# Adafruit_SHT31_Breakout.net
KiCad netlist of a schematic drawn in EAGLE
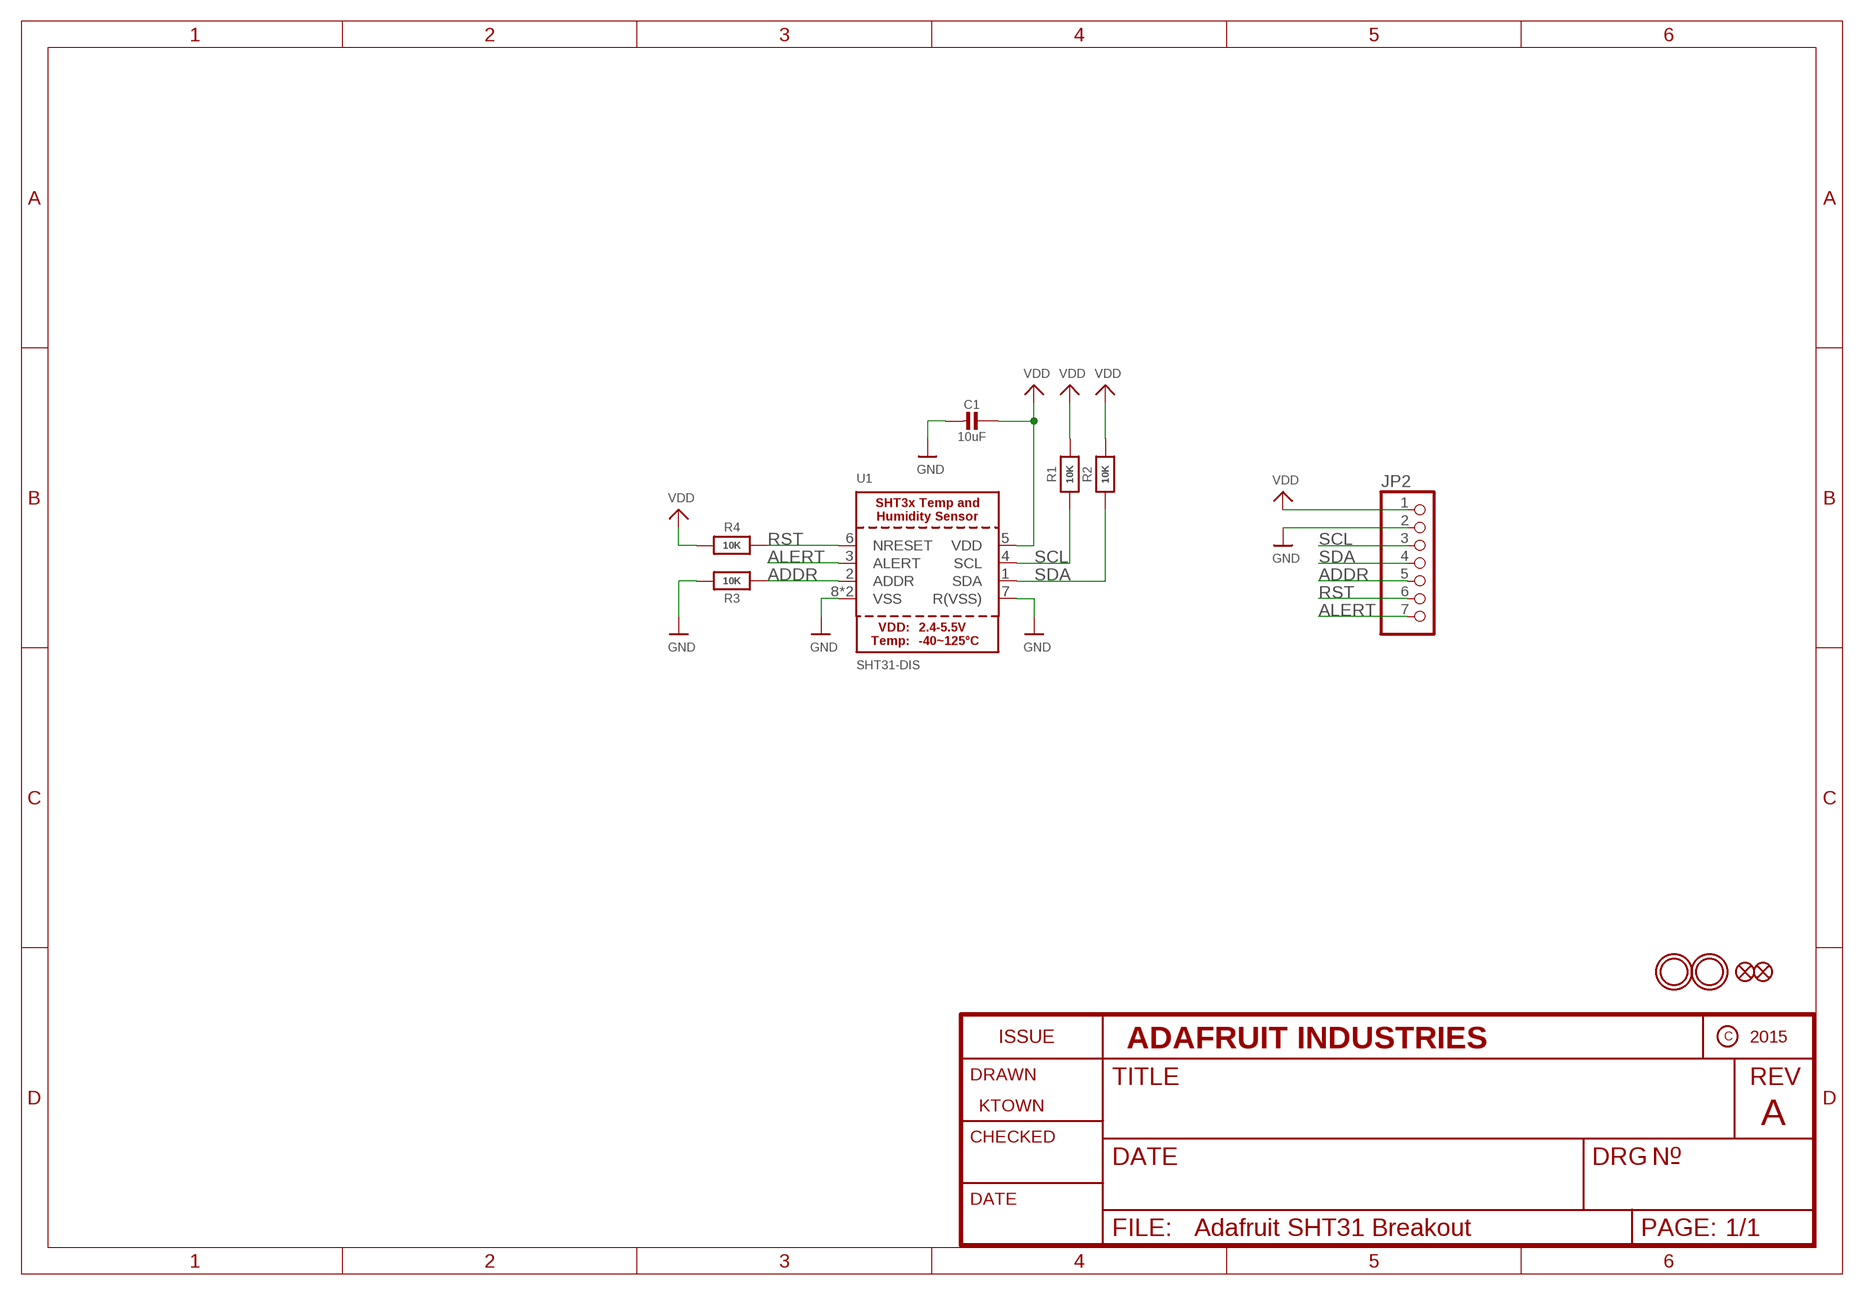
[diagram p0: schematic, sheet 1]

(export (version "E")
  (design (tool "Eeschema 10.0.6"))
  (components
    (comp (ref "C1")
      (value "10uF")
      (footprint "eagle-import:0805-NO")
      (libsource (lib "eagle-import") (part "CAP_CERAMIC0805-NOOUTLINE"))
    )
    (comp (ref "FID2")
      (value "FIDUCIAL\"\"")
      (footprint "eagle-import:FIDUCIAL_1MM")
      (libsource (lib "eagle-import") (part "FIDUCIAL{dblquote}{dblquote}"))
    )
    (comp (ref "FID3")
      (value "FIDUCIAL\"\"")
      (footprint "eagle-import:FIDUCIAL_1MM")
      (libsource (lib "eagle-import") (part "FIDUCIAL{dblquote}{dblquote}"))
    )
    (comp (ref "JP2")
      (value "HEADER-1X770MIL")
      (footprint "eagle-import:1X07_ROUND_70")
      (libsource (lib "eagle-import") (part "HEADER-1X770MIL"))
    )
    (comp (ref "R1")
      (value "10K")
      (footprint "eagle-import:0805-NO")
      (libsource (lib "eagle-import") (part "RESISTOR0805_NOOUTLINE"))
    )
    (comp (ref "R2")
      (value "10K")
      (footprint "eagle-import:0805-NO")
      (libsource (lib "eagle-import") (part "RESISTOR0805_NOOUTLINE"))
    )
    (comp (ref "R3")
      (value "10K")
      (footprint "eagle-import:_0805MP")
      (libsource (lib "eagle-import") (part "RESISTOR_0805MP"))
    )
    (comp (ref "R4")
      (value "10K")
      (footprint "eagle-import:0805-NO")
      (libsource (lib "eagle-import") (part "RESISTOR0805_NOOUTLINE"))
    )
    (comp (ref "U$1")
      (value "MOUNTINGHOLE2.5")
      (footprint "eagle-import:MOUNTINGHOLE_2.5_PLATED")
      (libsource (lib "eagle-import") (part "MOUNTINGHOLE2.5"))
    )
    (comp (ref "U$2")
      (value "MOUNTINGHOLE2.5")
      (footprint "eagle-import:MOUNTINGHOLE_2.5_PLATED")
      (libsource (lib "eagle-import") (part "MOUNTINGHOLE2.5"))
    )
    (comp (ref "U1")
      (value "SHT31-DIS")
      (footprint "eagle-import:SHT3X")
      (libsource (lib "eagle-import") (part "SHT3X"))
    )
  )
  (nets
    (net (code "1") (name "/ADDR") (class "Default")
      (node (ref "JP2") (pin "5") (pinfunction "5_5") (pintype "passive"))
      (node (ref "R3") (pin "1") (pinfunction "1_1") (pintype "passive"))
      (node (ref "U1") (pin "2") (pinfunction "ADDR_2") (pintype "bidirectional"))
    )
    (net (code "2") (name "/ALERT") (class "Default")
      (node (ref "JP2") (pin "7") (pinfunction "7_7") (pintype "passive"))
      (node (ref "U1") (pin "3") (pinfunction "ALERT_3") (pintype "bidirectional"))
    )
    (net (code "3") (name "/RST") (class "Default")
      (node (ref "JP2") (pin "6") (pinfunction "6_6") (pintype "passive"))
      (node (ref "R4") (pin "2") (pinfunction "2_2") (pintype "passive"))
      (node (ref "U1") (pin "6") (pinfunction "NRESET_6") (pintype "bidirectional"))
    )
    (net (code "4") (name "/SCL") (class "Default")
      (node (ref "JP2") (pin "3") (pinfunction "3_3") (pintype "passive"))
      (node (ref "R1") (pin "1") (pinfunction "1_1") (pintype "passive"))
      (node (ref "U1") (pin "4") (pinfunction "SCL_4") (pintype "bidirectional"))
    )
    (net (code "5") (name "/SDA") (class "Default")
      (node (ref "JP2") (pin "4") (pinfunction "4_4") (pintype "passive"))
      (node (ref "R2") (pin "1") (pinfunction "1_1") (pintype "passive"))
      (node (ref "U1") (pin "1") (pinfunction "SDA_1") (pintype "bidirectional"))
    )
    (net (code "6") (name "GND") (class "Default")
      (node (ref "C1") (pin "2") (pinfunction "2_2") (pintype "passive"))
      (node (ref "JP2") (pin "2") (pinfunction "2_2") (pintype "passive"))
      (node (ref "R3") (pin "2") (pinfunction "2_2") (pintype "passive"))
      (node (ref "U1") (pin "7") (pinfunction "R(VSS)_7") (pintype "bidirectional"))
      (node (ref "U1") (pin "8") (pinfunction "VSS_8") (pintype "power_in"))
      (node (ref "U1") (pin "THERMAL") (pinfunction "VSS_THERMAL") (pintype "power_in"))
    )
    (net (code "7") (name "VDD") (class "Default")
      (node (ref "C1") (pin "1") (pinfunction "1_1") (pintype "passive"))
      (node (ref "JP2") (pin "1") (pinfunction "1_1") (pintype "passive"))
      (node (ref "R1") (pin "2") (pinfunction "2_2") (pintype "passive"))
      (node (ref "R2") (pin "2") (pinfunction "2_2") (pintype "passive"))
      (node (ref "R4") (pin "1") (pinfunction "1_1") (pintype "passive"))
      (node (ref "U1") (pin "5") (pinfunction "VDD_5") (pintype "power_in"))
    )
  )
)
